# v3.net
KiCad netlist of a schematic drawn in EAGLE
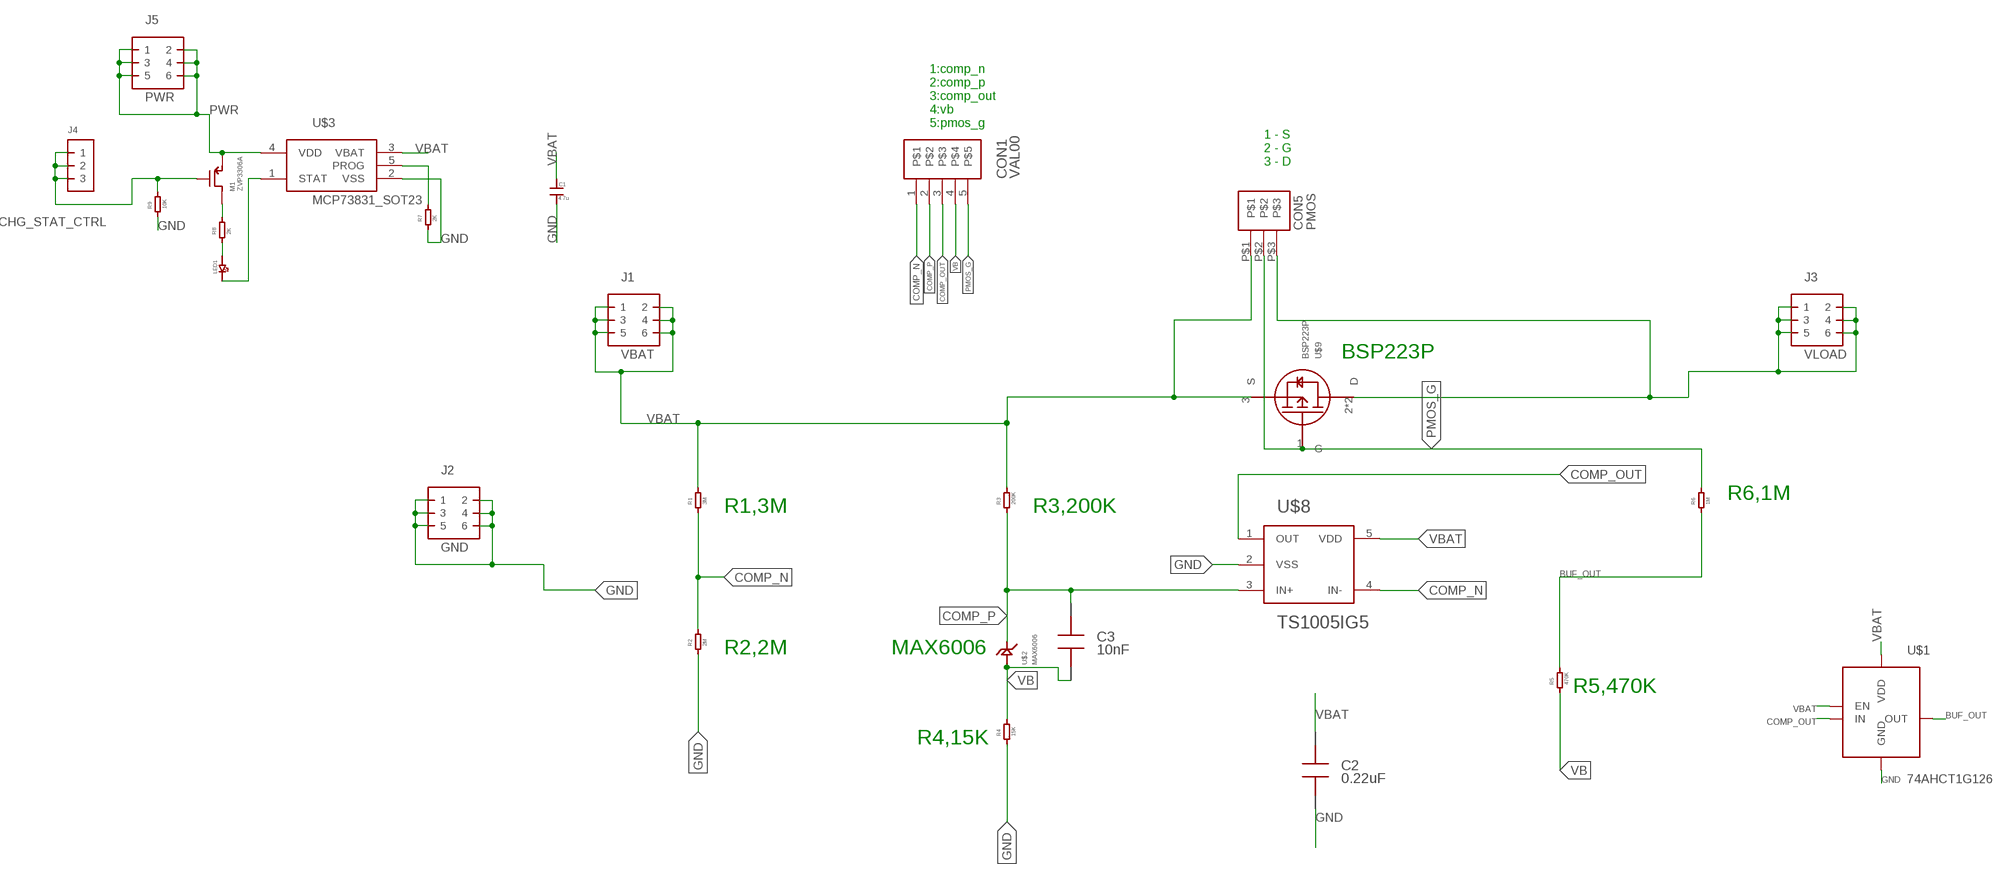
[diagram p0: schematic, sheet 1]

(export (version "E")
  (design (tool "Eeschema 10.0.6"))
  (components
    (comp (ref "C1")
      (value "4.7u")
      (footprint "eagle-import:GRM21")
      (libsource (lib "eagle-import") (part "GENERIC2012MM"))
    )
    (comp (ref "C2")
      (value "0.22uF")
      (footprint "eagle-import:UMK212F224ZD-T")
      (libsource (lib "eagle-import") (part "UMK212F224ZD-T"))
    )
    (comp (ref "C3")
      (value "10nF")
      (footprint "eagle-import:WALSIN_CAP_0805(2012MM)")
      (libsource (lib "eagle-import") (part "WALSIN_CAP_10NF"))
    )
    (comp (ref "CON1")
      (value "VAL00")
      (footprint "eagle-import:1X05_PH_2.54MM")
      (libsource (lib "eagle-import") (part "PINHD-1X5"))
    )
    (comp (ref "CON5")
      (value "PMOS")
      (footprint "eagle-import:1X03_PH_2.54MM")
      (libsource (lib "eagle-import") (part "PINHD-1X3"))
    )
    (comp (ref "J1")
      (value "VBAT")
      (footprint "eagle-import:2X3_2.54MM")
      (libsource (lib "eagle-import") (part "2X3_2.54MM"))
    )
    (comp (ref "J2")
      (value "GND")
      (footprint "eagle-import:2X3_2.54MM")
      (libsource (lib "eagle-import") (part "2X3_2.54MM"))
    )
    (comp (ref "J3")
      (value "VLOAD")
      (footprint "eagle-import:2X3_2.54MM")
      (libsource (lib "eagle-import") (part "2X3_2.54MM"))
    )
    (comp (ref "J4")
      (value "1X3_2.54MM")
      (footprint "eagle-import:1X3_2.54MM")
      (libsource (lib "eagle-import") (part "1X3_2.54MM"))
    )
    (comp (ref "J5")
      (value "PWR")
      (footprint "eagle-import:2X3_2.54MM")
      (libsource (lib "eagle-import") (part "2X3_2.54MM"))
    )
    (comp (ref "LED1")
      (value "LG_R971-KN-1")
      (footprint "eagle-import:LG_R971-KN-1_2012")
      (libsource (lib "eagle-import") (part "LG_R971-KN-1"))
    )
    (comp (ref "M1")
      (value "ZVP3306A")
      (footprint "eagle-import:ZVP3306A-TO92_2.54MM")
      (libsource (lib "eagle-import") (part "ZVP3306A_TO92_2.54MM"))
    )
    (comp (ref "R1")
      (value "3M")
      (footprint "eagle-import:ERJ2012")
      (libsource (lib "eagle-import") (part "R_GENERIC2012MM"))
    )
    (comp (ref "R2")
      (value "2M")
      (footprint "eagle-import:ERJ2012")
      (libsource (lib "eagle-import") (part "R_GENERIC2012MM"))
    )
    (comp (ref "R3")
      (value "200K")
      (footprint "eagle-import:ERJ2012")
      (libsource (lib "eagle-import") (part "R_GENERIC2012MM"))
    )
    (comp (ref "R4")
      (value "15K")
      (footprint "eagle-import:ERJ2012")
      (libsource (lib "eagle-import") (part "R_GENERIC2012MM"))
    )
    (comp (ref "R5")
      (value "470K")
      (footprint "eagle-import:ERJ2012")
      (libsource (lib "eagle-import") (part "R_GENERIC2012MM"))
    )
    (comp (ref "R6")
      (value "1M")
      (footprint "eagle-import:ERJ2012")
      (libsource (lib "eagle-import") (part "R_GENERIC2012MM"))
    )
    (comp (ref "R7")
      (value "2K")
      (footprint "eagle-import:ERJ2012")
      (libsource (lib "eagle-import") (part "R_GENERIC2012MM"))
    )
    (comp (ref "R8")
      (value "2K")
      (footprint "eagle-import:ERJ2012")
      (libsource (lib "eagle-import") (part "R_GENERIC2012MM"))
    )
    (comp (ref "R9")
      (value "10K")
      (footprint "eagle-import:ERJ2012")
      (libsource (lib "eagle-import") (part "R_GENERIC2012MM"))
    )
    (comp (ref "U$1")
      (value "74AHCT1G126")
      (footprint "eagle-import:74AHCT1G126-SOT353")
      (libsource (lib "eagle-import") (part "74AHCT1G126_SOT353"))
    )
    (comp (ref "U$2")
      (value "MAX6006")
      (footprint "eagle-import:8_SO_LP_90_0096")
      (libsource (lib "eagle-import") (part "MAX6006_8SO"))
    )
    (comp (ref "U$3")
      (value "MCP73831_SOT23")
      (footprint "eagle-import:MICROCHIP-SOT-23")
      (libsource (lib "eagle-import") (part "MCP73831_SOT23"))
    )
    (comp (ref "U$8")
      (value "TS1005IG5")
      (footprint "eagle-import:SILICONLABS-SOT23-5-G5_CUSTOM_V1")
      (libsource (lib "eagle-import") (part "TS1005IG5CUSTOM_V1"))
    )
    (comp (ref "U$9")
      (value "BSP223P")
      (footprint "eagle-import:INFINION-PG-SOT-223-4N")
      (libsource (lib "eagle-import") (part "BSP322PSMD"))
    )
  )
  (nets
    (net (code "1") (name "/BUF_OUT") (class "Default")
      (node (ref "R5") (pin "P$1") (pinfunction "1_P$1") (pintype "bidirectional"))
      (node (ref "R6") (pin "P$2") (pinfunction "2_P$2") (pintype "bidirectional"))
      (node (ref "U$1") (pin "4") (pinfunction "OUT_4") (pintype "bidirectional"))
    )
    (net (code "2") (name "/CHG_STAT_CTRL") (class "Default")
      (node (ref "J4") (pin "P$1") (pinfunction "1_P$1") (pintype "bidirectional"))
      (node (ref "J4") (pin "P$2") (pinfunction "2_P$2") (pintype "bidirectional"))
      (node (ref "J4") (pin "P$3") (pinfunction "3_P$3") (pintype "bidirectional"))
      (node (ref "M1") (pin "G") (pinfunction "G_G") (pintype "bidirectional"))
      (node (ref "R9") (pin "P$1") (pinfunction "1_P$1") (pintype "bidirectional"))
    )
    (net (code "3") (name "/PWR") (class "Default")
      (node (ref "J5") (pin "P$1") (pinfunction "1_P$1") (pintype "bidirectional"))
      (node (ref "J5") (pin "P$2") (pinfunction "2_P$2") (pintype "bidirectional"))
      (node (ref "J5") (pin "P$3") (pinfunction "3_P$3") (pintype "bidirectional"))
      (node (ref "J5") (pin "P$4") (pinfunction "4_P$4") (pintype "bidirectional"))
      (node (ref "J5") (pin "P$5") (pinfunction "5_P$5") (pintype "bidirectional"))
      (node (ref "J5") (pin "P$6") (pinfunction "6_P$6") (pintype "bidirectional"))
      (node (ref "M1") (pin "S") (pinfunction "S_S") (pintype "bidirectional"))
      (node (ref "U$3") (pin "4") (pinfunction "VDD_4") (pintype "bidirectional"))
    )
    (net (code "4") (name "COMP_N") (class "Default")
      (node (ref "CON1") (pin "1") (pinfunction "P$1_1") (pintype "bidirectional"))
      (node (ref "R1") (pin "P$2") (pinfunction "2_P$2") (pintype "bidirectional"))
      (node (ref "R2") (pin "P$1") (pinfunction "1_P$1") (pintype "bidirectional"))
      (node (ref "U$8") (pin "4") (pinfunction "IN-_4") (pintype "bidirectional"))
    )
    (net (code "5") (name "COMP_OUT") (class "Default")
      (node (ref "CON1") (pin "3") (pinfunction "P$3_3") (pintype "bidirectional"))
      (node (ref "U$1") (pin "2") (pinfunction "IN_2") (pintype "bidirectional"))
      (node (ref "U$8") (pin "1") (pinfunction "OUT_1") (pintype "bidirectional"))
    )
    (net (code "6") (name "COMP_P") (class "Default")
      (node (ref "C3") (pin "P$1") (pinfunction "P$1_P$1") (pintype "bidirectional"))
      (node (ref "CON1") (pin "2") (pinfunction "P$2_2") (pintype "bidirectional"))
      (node (ref "R3") (pin "P$2") (pinfunction "2_P$2") (pintype "bidirectional"))
      (node (ref "U$2") (pin "6") (pinfunction "OUT_6") (pintype "bidirectional"))
      (node (ref "U$2") (pin "8") (pinfunction "OUT_8") (pintype "bidirectional"))
      (node (ref "U$8") (pin "3") (pinfunction "IN+_3") (pintype "bidirectional"))
    )
    (net (code "7") (name "GND") (class "Default")
      (node (ref "C1") (pin "P$2") (pinfunction "2_P$2") (pintype "bidirectional"))
      (node (ref "C2") (pin "P$2") (pinfunction "P$2_P$2") (pintype "bidirectional"))
      (node (ref "J2") (pin "P$1") (pinfunction "1_P$1") (pintype "bidirectional"))
      (node (ref "J2") (pin "P$2") (pinfunction "2_P$2") (pintype "bidirectional"))
      (node (ref "J2") (pin "P$3") (pinfunction "3_P$3") (pintype "bidirectional"))
      (node (ref "J2") (pin "P$4") (pinfunction "4_P$4") (pintype "bidirectional"))
      (node (ref "J2") (pin "P$5") (pinfunction "5_P$5") (pintype "bidirectional"))
      (node (ref "J2") (pin "P$6") (pinfunction "6_P$6") (pintype "bidirectional"))
      (node (ref "R2") (pin "P$2") (pinfunction "2_P$2") (pintype "bidirectional"))
      (node (ref "R4") (pin "P$2") (pinfunction "2_P$2") (pintype "bidirectional"))
      (node (ref "R7") (pin "P$2") (pinfunction "2_P$2") (pintype "bidirectional"))
      (node (ref "R9") (pin "P$2") (pinfunction "2_P$2") (pintype "bidirectional"))
      (node (ref "U$1") (pin "3") (pinfunction "GND_3") (pintype "bidirectional"))
      (node (ref "U$3") (pin "2") (pinfunction "VSS_2") (pintype "bidirectional"))
      (node (ref "U$8") (pin "2") (pinfunction "VSS_2") (pintype "bidirectional"))
    )
    (net (code "8") (name "Net-(J3-1)") (class "Default")
      (node (ref "CON5") (pin "P$3") (pinfunction "P$3_P$3") (pintype "bidirectional"))
      (node (ref "J3") (pin "P$1") (pinfunction "1_P$1") (pintype "bidirectional"))
      (node (ref "J3") (pin "P$2") (pinfunction "2_P$2") (pintype "bidirectional"))
      (node (ref "J3") (pin "P$3") (pinfunction "3_P$3") (pintype "bidirectional"))
      (node (ref "J3") (pin "P$4") (pinfunction "4_P$4") (pintype "bidirectional"))
      (node (ref "J3") (pin "P$5") (pinfunction "5_P$5") (pintype "bidirectional"))
      (node (ref "J3") (pin "P$6") (pinfunction "6_P$6") (pintype "bidirectional"))
      (node (ref "U$9") (pin "2") (pinfunction "D_2") (pintype "bidirectional"))
      (node (ref "U$9") (pin "4") (pinfunction "D_4") (pintype "bidirectional"))
    )
    (net (code "9") (name "Net-(LED1-CURRENT_IN)") (class "Default")
      (node (ref "LED1") (pin "A") (pinfunction "CURRENT_IN_A") (pintype "bidirectional"))
      (node (ref "R8") (pin "P$2") (pinfunction "2_P$2") (pintype "bidirectional"))
    )
    (net (code "10") (name "Net-(LED1-CURRENT_OUT)") (class "Default")
      (node (ref "LED1") (pin "C") (pinfunction "CURRENT_OUT_C") (pintype "bidirectional"))
      (node (ref "U$3") (pin "1") (pinfunction "STAT_1") (pintype "bidirectional"))
    )
    (net (code "11") (name "Net-(R7-1)") (class "Default")
      (node (ref "R7") (pin "P$1") (pinfunction "1_P$1") (pintype "bidirectional"))
      (node (ref "U$3") (pin "5") (pinfunction "PROG_5") (pintype "bidirectional"))
    )
    (net (code "12") (name "Net-(R8-1)") (class "Default")
      (node (ref "M1") (pin "D") (pinfunction "D_D") (pintype "bidirectional"))
      (node (ref "R8") (pin "P$1") (pinfunction "1_P$1") (pintype "bidirectional"))
    )
    (net (code "13") (name "PMOS_G") (class "Default")
      (node (ref "CON1") (pin "5") (pinfunction "P$5_5") (pintype "bidirectional"))
      (node (ref "CON5") (pin "P$2") (pinfunction "P$2_P$2") (pintype "bidirectional"))
      (node (ref "R6") (pin "P$1") (pinfunction "1_P$1") (pintype "bidirectional"))
      (node (ref "U$9") (pin "1") (pinfunction "G_1") (pintype "bidirectional"))
    )
    (net (code "14") (name "VB") (class "Default")
      (node (ref "C3") (pin "P$2") (pinfunction "P$2_P$2") (pintype "bidirectional"))
      (node (ref "CON1") (pin "4") (pinfunction "P$4_4") (pintype "bidirectional"))
      (node (ref "R4") (pin "P$1") (pinfunction "1_P$1") (pintype "bidirectional"))
      (node (ref "R5") (pin "P$2") (pinfunction "2_P$2") (pintype "bidirectional"))
      (node (ref "U$2") (pin "4") (pinfunction "GND_4") (pintype "bidirectional"))
    )
    (net (code "15") (name "VBAT") (class "Default")
      (node (ref "C1") (pin "P$1") (pinfunction "1_P$1") (pintype "bidirectional"))
      (node (ref "C2") (pin "P$1") (pinfunction "P$1_P$1") (pintype "bidirectional"))
      (node (ref "CON5") (pin "P$1") (pinfunction "P$1_P$1") (pintype "bidirectional"))
      (node (ref "J1") (pin "P$1") (pinfunction "1_P$1") (pintype "bidirectional"))
      (node (ref "J1") (pin "P$2") (pinfunction "2_P$2") (pintype "bidirectional"))
      (node (ref "J1") (pin "P$3") (pinfunction "3_P$3") (pintype "bidirectional"))
      (node (ref "J1") (pin "P$4") (pinfunction "4_P$4") (pintype "bidirectional"))
      (node (ref "J1") (pin "P$5") (pinfunction "5_P$5") (pintype "bidirectional"))
      (node (ref "J1") (pin "P$6") (pinfunction "6_P$6") (pintype "bidirectional"))
      (node (ref "R1") (pin "P$1") (pinfunction "1_P$1") (pintype "bidirectional"))
      (node (ref "R3") (pin "P$1") (pinfunction "1_P$1") (pintype "bidirectional"))
      (node (ref "U$1") (pin "1") (pinfunction "EN_1") (pintype "bidirectional"))
      (node (ref "U$1") (pin "5") (pinfunction "VDD_5") (pintype "bidirectional"))
      (node (ref "U$3") (pin "3") (pinfunction "VBAT_3") (pintype "bidirectional"))
      (node (ref "U$8") (pin "5") (pinfunction "VDD_5") (pintype "bidirectional"))
      (node (ref "U$9") (pin "3") (pinfunction "S_3") (pintype "bidirectional"))
    )
  )
)
